# alarm_to_uart.net
KiCad netlist of a schematic drawn in Altium Designer
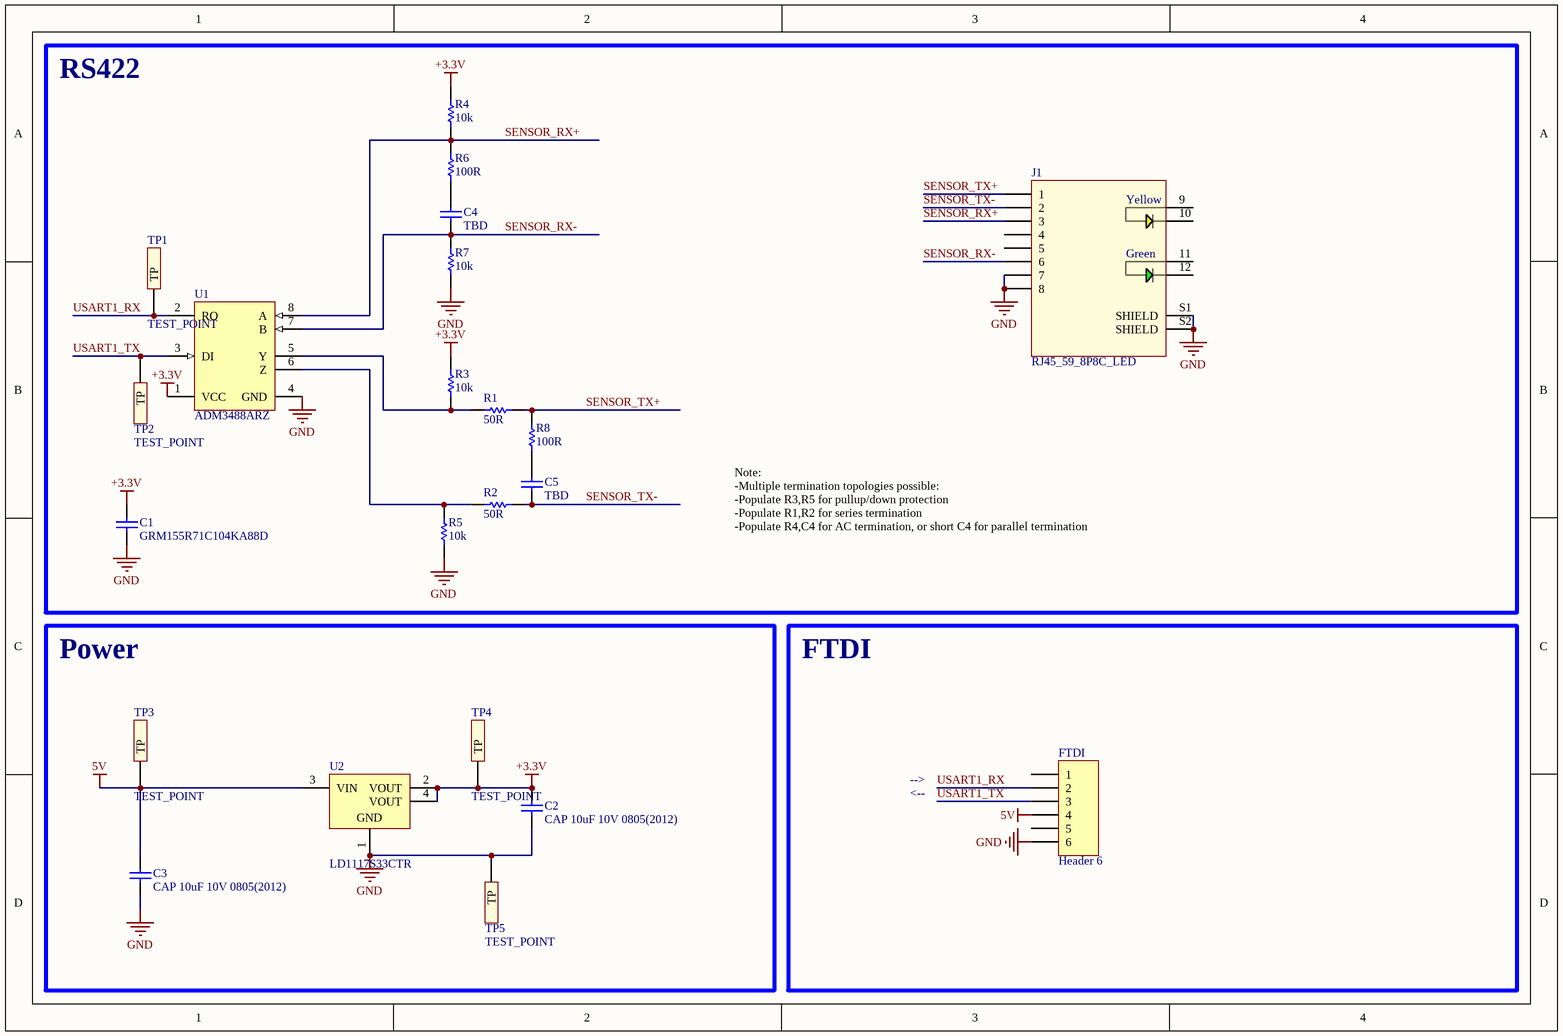
[diagram p0: alarm_to_uart.SchDoc]

(export (version "E")
  (design (tool "Eeschema 10.0.6"))
  (components
    (comp (ref "C1")
      (value "GRM155R71C104KA88D")
      (footprint "CAPC1005X55X25ML05T10")
      (description "Chip Capacitor, 0.1 uF, +/- 10%, 16 V, -55 to 125 degC, 0402 (1005 Metric), RoHS, Tape and Reel")
      (fields (field (name "VOLTAGE") "16V") (field (name "TOLERANCE") "10%"))
      (libsource (lib "Altium Content Vault") (part "CAP-NP-2"))
    )
    (comp (ref "C2")
      (value "CAP 10uF 10V 0805(2012)")
      (footprint "CAPC0805(2012)145_N")
      (description "CAP 10uF 10V ±10% 0805 (2012 Metric) Thickness 1.45mm SMD")
      (fields (field (name "TOLERANCE") "Â±10%"))
      (libsource (lib "Altium Content Vault") (part "CAP"))
    )
    (comp (ref "C3")
      (value "CAP 10uF 10V 0805(2012)")
      (footprint "CAPC0805(2012)145_N")
      (description "CAP 10uF 10V ±10% 0805 (2012 Metric) Thickness 1.45mm SMD")
      (fields (field (name "TOLERANCE") "Â±10%"))
      (libsource (lib "Altium Content Vault") (part "CAP"))
    )
    (comp (ref "C4")
      (value "TBD")
      (footprint "CAPC1005X55X25ML05T10")
      (description "Chip Capacitor, 0.1 uF, +/- 10%, 16 V, -55 to 125 degC, 0402 (1005 Metric), RoHS, Tape and Reel")
      (fields (field (name "VOLTAGE") "16V") (field (name "TOLERANCE") "10%"))
      (libsource (lib "Altium Content Vault") (part "CAP-NP-2"))
    )
    (comp (ref "C5")
      (value "TBD")
      (footprint "CAPC1005X55X25ML05T10")
      (description "Chip Capacitor, 0.1 uF, +/- 10%, 16 V, -55 to 125 degC, 0402 (1005 Metric), RoHS, Tape and Reel")
      (fields (field (name "VOLTAGE") "16V") (field (name "TOLERANCE") "10%"))
      (libsource (lib "Altium Content Vault") (part "CAP-NP-2"))
    )
    (comp (ref "FTDI")
      (value "Header 6")
      (footprint "HDR1X6")
      (description "Header, 6-Pin")
      (fields (field (name "PUBLISHER") "Altium Limited"))
      (libsource (lib "Miscellaneous Connectors") (part "Header 6"))
    )
    (comp (ref "J1")
      (value "RJ45_59_8P8C_LED")
      (footprint "RJ45_59_8P8C_LED")
      (description "Generic RJ49 jack with LED and without magnetics")
      (fields (field (name "MANUFACTURER") "Unknown/Generic"))
      (libsource (lib "Blinkinlabs") (part "RJ45_59_8P8C_LED"))
    )
    (comp (ref "R1")
      (value "50R")
      (footprint "RESC0603(1608)_L")
      (description "120R 0.1W 5% 0603 (1608 Metric)  SMD")
      (fields (field (name "POWER") "0.1 W") (field (name "TOLERANCE") "5 %"))
      (libsource (lib "Altium Content Vault") (part "RES"))
    )
    (comp (ref "R2")
      (value "50R")
      (footprint "RESC0603(1608)_L")
      (description "120R 0.1W 5% 0603 (1608 Metric)  SMD")
      (fields (field (name "POWER") "0.1 W") (field (name "TOLERANCE") "5 %"))
      (libsource (lib "Altium Content Vault") (part "RES"))
    )
    (comp (ref "R3")
      (value "10k")
      (footprint "RESC0603(1608)_L")
      (description "120R 0.1W 5% 0603 (1608 Metric)  SMD")
      (fields (field (name "POWER") "0.1 W") (field (name "TOLERANCE") "5 %"))
      (libsource (lib "Altium Content Vault") (part "RES"))
    )
    (comp (ref "R4")
      (value "10k")
      (footprint "RESC0603(1608)_L")
      (description "120R 0.1W 5% 0603 (1608 Metric)  SMD")
      (fields (field (name "POWER") "0.1 W") (field (name "TOLERANCE") "5 %"))
      (libsource (lib "Altium Content Vault") (part "RES"))
    )
    (comp (ref "R5")
      (value "10k")
      (footprint "RESC0603(1608)_L")
      (description "120R 0.1W 5% 0603 (1608 Metric)  SMD")
      (fields (field (name "POWER") "0.1 W") (field (name "TOLERANCE") "5 %"))
      (libsource (lib "Altium Content Vault") (part "RES"))
    )
    (comp (ref "R6")
      (value "100R")
      (footprint "RESC0603(1608)_L")
      (description "120R 0.1W 5% 0603 (1608 Metric)  SMD")
      (fields (field (name "POWER") "0.1 W") (field (name "TOLERANCE") "5 %"))
      (libsource (lib "Altium Content Vault") (part "RES"))
    )
    (comp (ref "R7")
      (value "10k")
      (footprint "RESC0603(1608)_L")
      (description "120R 0.1W 5% 0603 (1608 Metric)  SMD")
      (fields (field (name "POWER") "0.1 W") (field (name "TOLERANCE") "5 %"))
      (libsource (lib "Altium Content Vault") (part "RES"))
    )
    (comp (ref "R8")
      (value "100R")
      (footprint "RESC0603(1608)_L")
      (description "120R 0.1W 5% 0603 (1608 Metric)  SMD")
      (fields (field (name "POWER") "0.1 W") (field (name "TOLERANCE") "5 %"))
      (libsource (lib "Altium Content Vault") (part "RES"))
    )
    (comp (ref "TP1")
      (value "TEST_POINT")
      (footprint "TP-SMD-1mm")
      (description "Test point")
      (libsource (lib "") (part "TEST_POINT_1"))
    )
    (comp (ref "TP2")
      (value "TEST_POINT")
      (footprint "TP-SMD-1mm")
      (description "Test point")
      (libsource (lib "Blinkinlabs") (part "TEST_POINT"))
    )
    (comp (ref "TP3")
      (value "TEST_POINT")
      (footprint "TP-SMD-1mm")
      (description "Test point")
      (libsource (lib "") (part "TEST_POINT_1"))
    )
    (comp (ref "TP4")
      (value "TEST_POINT")
      (footprint "TP-SMD-1mm")
      (description "Test point")
      (libsource (lib "") (part "TEST_POINT_1"))
    )
    (comp (ref "TP5")
      (value "TEST_POINT")
      (footprint "TP-SMD-1mm")
      (description "Test point")
      (libsource (lib "Blinkinlabs") (part "TEST_POINT"))
    )
    (comp (ref "U1")
      (value "ADM3488ARZ")
      (footprint "ADI-R-8_L")
      (fields (field (name "MANUFACTURER") "Analog Devices"))
      (libsource (lib "Altium Content Vault") (part "ADI-ADM3488_90-R-8"))
    )
    (comp (ref "U2")
      (value "LD1117S33CTR")
      (footprint "SOT-223_N")
      (description "Fixed Low Drop Positive Voltage Regulator, 3.3V, 4-Pin SOT-223, Tape and Reel")
      (libsource (lib "Altium Content Vault") (part "PM-REG-LD1117-SOT4"))
    )
  )
  (nets
    (net (code "1") (name "+3.3V") (class "Default")
      (node (ref "C1") (pin "2") (pinfunction "2_2") (pintype "passive"))
      (node (ref "C2") (pin "2") (pinfunction "2_2") (pintype "passive"))
      (node (ref "R3") (pin "1") (pinfunction "1_1") (pintype "passive"))
      (node (ref "R4") (pin "1") (pinfunction "1_1") (pintype "passive"))
      (node (ref "TP4") (pin "1") (pinfunction "TP_1") (pintype "passive"))
      (node (ref "U1") (pin "1") (pinfunction "VCC_1") (pintype "power_in"))
      (node (ref "U2") (pin "2") (pinfunction "VOUT_2") (pintype "power_in"))
      (node (ref "U2") (pin "4") (pinfunction "VOUT_4") (pintype "power_in"))
    )
    (net (code "2") (name "/SENSOR_RX+") (class "Default")
      (node (ref "J1") (pin "3") (pinfunction "3_3") (pintype "passive"))
      (node (ref "R4") (pin "2") (pinfunction "2_2") (pintype "passive"))
      (node (ref "R6") (pin "1") (pinfunction "1_1") (pintype "passive"))
      (node (ref "U1") (pin "8") (pinfunction "A_8") (pintype "input"))
    )
    (net (code "3") (name "/SENSOR_RX-") (class "Default")
      (node (ref "C4") (pin "1") (pinfunction "1_1") (pintype "passive"))
      (node (ref "J1") (pin "6") (pinfunction "6_6") (pintype "passive"))
      (node (ref "R7") (pin "1") (pinfunction "1_1") (pintype "passive"))
      (node (ref "U1") (pin "7") (pinfunction "B_7") (pintype "input"))
    )
    (net (code "4") (name "/SENSOR_TX+") (class "Default")
      (node (ref "J1") (pin "1") (pinfunction "1_1") (pintype "passive"))
      (node (ref "R1") (pin "1") (pinfunction "1_1") (pintype "passive"))
      (node (ref "R8") (pin "1") (pinfunction "1_1") (pintype "passive"))
    )
    (net (code "5") (name "/SENSOR_TX-") (class "Default")
      (node (ref "C5") (pin "1") (pinfunction "1_1") (pintype "passive"))
      (node (ref "J1") (pin "2") (pinfunction "2_2") (pintype "passive"))
      (node (ref "R2") (pin "1") (pinfunction "1_1") (pintype "passive"))
    )
    (net (code "6") (name "/USART1_RX") (class "Default")
      (node (ref "FTDI") (pin "2") (pinfunction "2_2") (pintype "passive"))
      (node (ref "TP1") (pin "1") (pinfunction "TP_1") (pintype "passive"))
      (node (ref "U1") (pin "2") (pinfunction "RO_2") (pintype "tri_state"))
    )
    (net (code "7") (name "/USART1_TX") (class "Default")
      (node (ref "FTDI") (pin "3") (pinfunction "3_3") (pintype "passive"))
      (node (ref "TP2") (pin "1") (pinfunction "TP_1") (pintype "passive"))
      (node (ref "U1") (pin "3") (pinfunction "DI_3") (pintype "input"))
    )
    (net (code "8") (name "5V") (class "Default")
      (node (ref "C3") (pin "2") (pinfunction "2_2") (pintype "passive"))
      (node (ref "FTDI") (pin "4") (pinfunction "4_4") (pintype "passive"))
      (node (ref "TP3") (pin "1") (pinfunction "TP_1") (pintype "passive"))
      (node (ref "U2") (pin "3") (pinfunction "VIN_3") (pintype "power_in"))
    )
    (net (code "9") (name "GND") (class "Default")
      (node (ref "C1") (pin "1") (pinfunction "1_1") (pintype "passive"))
      (node (ref "C2") (pin "1") (pinfunction "1_1") (pintype "passive"))
      (node (ref "C3") (pin "1") (pinfunction "1_1") (pintype "passive"))
      (node (ref "FTDI") (pin "6") (pinfunction "6_6") (pintype "passive"))
      (node (ref "J1") (pin "7") (pinfunction "7_7") (pintype "passive"))
      (node (ref "J1") (pin "8") (pinfunction "8_8") (pintype "passive"))
      (node (ref "J1") (pin "S1") (pinfunction "SHIELD_S1") (pintype "passive"))
      (node (ref "J1") (pin "S2") (pinfunction "SHIELD_S2") (pintype "passive"))
      (node (ref "R5") (pin "2") (pinfunction "2_2") (pintype "passive"))
      (node (ref "R7") (pin "2") (pinfunction "2_2") (pintype "passive"))
      (node (ref "TP5") (pin "1") (pinfunction "TP_1") (pintype "passive"))
      (node (ref "U1") (pin "4") (pinfunction "GND_4") (pintype "power_in"))
      (node (ref "U2") (pin "1") (pinfunction "GND_1") (pintype "power_in"))
    )
    (net (code "10") (name "Net-(C4-Pad2)") (class "Default")
      (node (ref "C4") (pin "2") (pinfunction "2_2") (pintype "passive"))
      (node (ref "R6") (pin "2") (pinfunction "2_2") (pintype "passive"))
    )
    (net (code "11") (name "Net-(C5-Pad2)") (class "Default")
      (node (ref "C5") (pin "2") (pinfunction "2_2") (pintype "passive"))
      (node (ref "R8") (pin "2") (pinfunction "2_2") (pintype "passive"))
    )
    (net (code "12") (name "Net-(U1-Y)") (class "Default")
      (node (ref "R1") (pin "2") (pinfunction "2_2") (pintype "passive"))
      (node (ref "R3") (pin "2") (pinfunction "2_2") (pintype "passive"))
      (node (ref "U1") (pin "5") (pinfunction "Y_5") (pintype "tri_state"))
    )
    (net (code "13") (name "Net-(U1-Z)") (class "Default")
      (node (ref "R2") (pin "2") (pinfunction "2_2") (pintype "passive"))
      (node (ref "R5") (pin "1") (pinfunction "1_1") (pintype "passive"))
      (node (ref "U1") (pin "6") (pinfunction "Z_6") (pintype "tri_state"))
    )
    (net (code "14") (name "unconnected-(FTDI-Pad1)") (class "Default")
      (node (ref "FTDI") (pin "1") (pinfunction "1_1") (pintype "passive"))
    )
    (net (code "15") (name "unconnected-(FTDI-Pad5)") (class "Default")
      (node (ref "FTDI") (pin "5") (pinfunction "5_5") (pintype "passive"))
    )
    (net (code "16") (name "unconnected-(J1-Green_Anode-Pad11)") (class "Default")
      (node (ref "J1") (pin "11") (pinfunction "Green_Anode_11") (pintype "passive"))
    )
    (net (code "17") (name "unconnected-(J1-Green_Cathode-Pad12)") (class "Default")
      (node (ref "J1") (pin "12") (pinfunction "Green_Cathode_12") (pintype "passive"))
    )
    (net (code "18") (name "unconnected-(J1-Pad4)") (class "Default")
      (node (ref "J1") (pin "4") (pinfunction "4_4") (pintype "passive"))
    )
    (net (code "19") (name "unconnected-(J1-Pad5)") (class "Default")
      (node (ref "J1") (pin "5") (pinfunction "5_5") (pintype "passive"))
    )
    (net (code "20") (name "unconnected-(J1-Yellow_Anode-Pad9)") (class "Default")
      (node (ref "J1") (pin "9") (pinfunction "Yellow_Anode_9") (pintype "passive"))
    )
    (net (code "21") (name "unconnected-(J1-Yellow_Cathode-Pad10)") (class "Default")
      (node (ref "J1") (pin "10") (pinfunction "Yellow_Cathode_10") (pintype "passive"))
    )
  )
)
